# Audio_Devices.net
KiCad netlist of a schematic drawn in Altium Designer
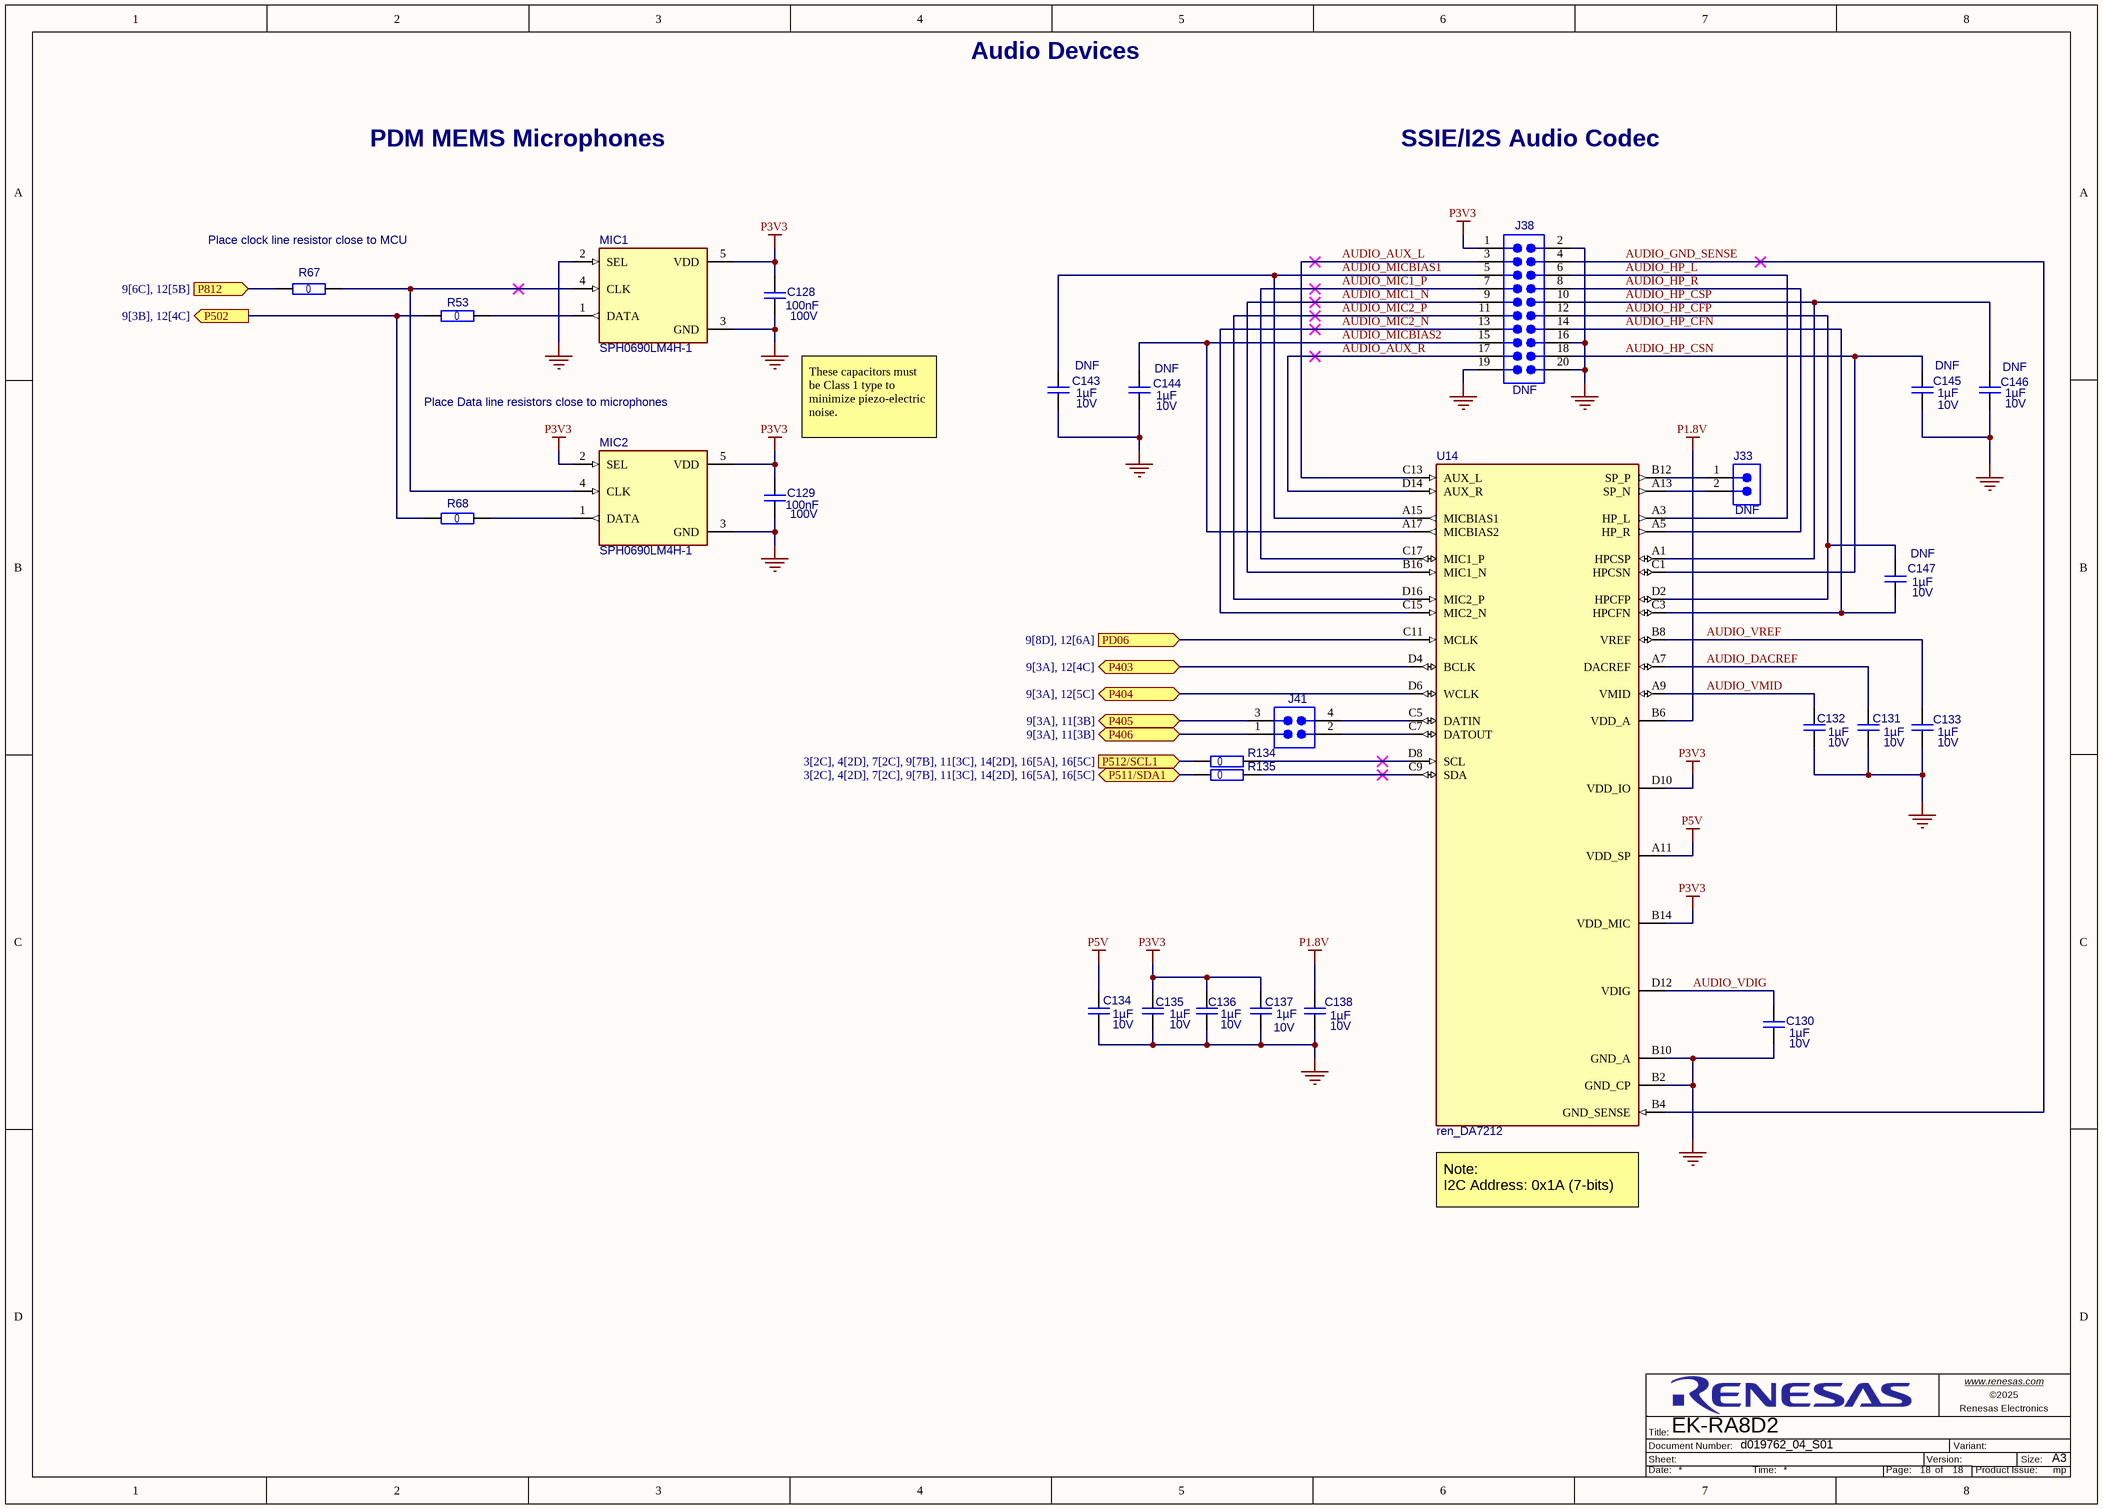
[diagram p0: Audio Devices.SchDoc]

(export (version "E")
  (design (tool "Eeschema 10.0.6"))
  (components
    (comp (ref "C128")
      (value "100nF")
      (footprint "C_EIA1206_1p8")
      (description "Capacitor,EIA1206,100n,100V,C0G")
      (fields
        (field (name "TOLERANCE") "5%")
        (field (name "OPERATING VOLTAGE MAX") "100V")
        (field (name "Comment") "Capacitor")
      )
      (libsource (lib "ek-ra8d2_mp - Customer") (part "Capacitor"))
    )
    (comp (ref "C129")
      (value "100nF")
      (footprint "C_EIA1206_1p8")
      (description "Capacitor,EIA1206,100n,100V,C0G")
      (fields
        (field (name "TOLERANCE") "5%")
        (field (name "OPERATING VOLTAGE MAX") "100V")
        (field (name "Comment") "Capacitor")
      )
      (libsource (lib "ek-ra8d2_mp - Customer") (part "Capacitor"))
    )
    (comp (ref "C130")
      (value "1µF")
      (footprint "C_EIA0201_0p4")
      (description "Capacitor,EA0201,1u,10V,X6S")
      (fields
        (field (name "TOLERANCE") "20%")
        (field (name "OPERATING VOLTAGE MAX") "10V")
        (field (name "Comment") "Capacitor")
      )
      (libsource (lib "ek-ra8d2_mp - Customer") (part "Capacitor"))
    )
    (comp (ref "C131")
      (value "1µF")
      (footprint "C_EIA0201_0p4")
      (description "Capacitor,EA0201,1u,10V,X6S")
      (fields
        (field (name "TOLERANCE") "20%")
        (field (name "OPERATING VOLTAGE MAX") "10V")
        (field (name "Comment") "Capacitor")
      )
      (libsource (lib "ek-ra8d2_mp - Customer") (part "Capacitor"))
    )
    (comp (ref "C132")
      (value "1µF")
      (footprint "C_EIA0201_0p4")
      (description "Capacitor,EA0201,1u,10V,X6S")
      (fields
        (field (name "TOLERANCE") "20%")
        (field (name "OPERATING VOLTAGE MAX") "10V")
        (field (name "Comment") "Capacitor")
      )
      (libsource (lib "ek-ra8d2_mp - Customer") (part "Capacitor"))
    )
    (comp (ref "C133")
      (value "1µF")
      (footprint "C_EIA0201_0p4")
      (description "Capacitor,EA0201,1u,10V,X6S")
      (fields
        (field (name "TOLERANCE") "20%")
        (field (name "OPERATING VOLTAGE MAX") "10V")
        (field (name "Comment") "Capacitor")
      )
      (libsource (lib "ek-ra8d2_mp - Customer") (part "Capacitor"))
    )
    (comp (ref "C134")
      (value "1µF")
      (footprint "C_EIA0201_0p4")
      (description "Capacitor,EA0201,1u,10V,X6S")
      (fields
        (field (name "TOLERANCE") "20%")
        (field (name "OPERATING VOLTAGE MAX") "10V")
        (field (name "Comment") "Capacitor")
      )
      (libsource (lib "ek-ra8d2_mp - Customer") (part "Capacitor"))
    )
    (comp (ref "C135")
      (value "1µF")
      (footprint "C_EIA0201_0p4")
      (description "Capacitor,EA0201,1u,10V,X6S")
      (fields
        (field (name "TOLERANCE") "20%")
        (field (name "OPERATING VOLTAGE MAX") "10V")
        (field (name "Comment") "Capacitor")
      )
      (libsource (lib "ek-ra8d2_mp - Customer") (part "Capacitor"))
    )
    (comp (ref "C136")
      (value "1µF")
      (footprint "C_EIA0201_0p4")
      (description "Capacitor,EA0201,1u,10V,X6S")
      (fields
        (field (name "TOLERANCE") "20%")
        (field (name "OPERATING VOLTAGE MAX") "10V")
        (field (name "Comment") "Capacitor")
      )
      (libsource (lib "ek-ra8d2_mp - Customer") (part "Capacitor"))
    )
    (comp (ref "C137")
      (value "1µF")
      (footprint "C_EIA0201_0p4")
      (description "Capacitor,EA0201,1u,10V,X6S")
      (fields
        (field (name "TOLERANCE") "20%")
        (field (name "OPERATING VOLTAGE MAX") "10V")
        (field (name "Comment") "Capacitor")
      )
      (libsource (lib "ek-ra8d2_mp - Customer") (part "Capacitor"))
    )
    (comp (ref "C138")
      (value "1µF")
      (footprint "C_EIA0201_0p4")
      (description "Capacitor,EA0201,1u,10V,X6S")
      (fields
        (field (name "TOLERANCE") "20%")
        (field (name "OPERATING VOLTAGE MAX") "10V")
        (field (name "Comment") "Capacitor")
      )
      (libsource (lib "ek-ra8d2_mp - Customer") (part "Capacitor"))
    )
    (comp (ref "C143")
      (value "1µF")
      (footprint "C_EIA0201_0p4")
      (description "Capacitor,EA0201,1u,10V,X6S")
      (fields
        (field (name "TOLERANCE") "20%")
        (field (name "OPERATING VOLTAGE MAX") "10V")
        (field (name "DNF") "DNF")
        (field (name "Comment") "Capacitor")
      )
      (libsource (lib "ek-ra8d2_mp - Customer") (part "Capacitor"))
    )
    (comp (ref "C144")
      (value "1µF")
      (footprint "C_EIA0201_0p4")
      (description "Capacitor,EA0201,1u,10V,X6S")
      (fields
        (field (name "TOLERANCE") "20%")
        (field (name "OPERATING VOLTAGE MAX") "10V")
        (field (name "DNF") "DNF")
        (field (name "Comment") "Capacitor")
      )
      (libsource (lib "ek-ra8d2_mp - Customer") (part "Capacitor"))
    )
    (comp (ref "C145")
      (value "1µF")
      (footprint "C_EIA0201_0p4")
      (description "Capacitor,EA0201,1u,10V,X6S")
      (fields
        (field (name "TOLERANCE") "20%")
        (field (name "OPERATING VOLTAGE MAX") "10V")
        (field (name "DNF") "DNF")
        (field (name "Comment") "Capacitor")
      )
      (libsource (lib "ek-ra8d2_mp - Customer") (part "Capacitor"))
    )
    (comp (ref "C146")
      (value "1µF")
      (footprint "C_EIA0201_0p4")
      (description "Capacitor,EA0201,1u,10V,X6S")
      (fields
        (field (name "TOLERANCE") "20%")
        (field (name "OPERATING VOLTAGE MAX") "10V")
        (field (name "DNF") "DNF")
        (field (name "Comment") "Capacitor")
      )
      (libsource (lib "ek-ra8d2_mp - Customer") (part "Capacitor"))
    )
    (comp (ref "C147")
      (value "1µF")
      (footprint "C_EIA0201_0p4")
      (description "Capacitor,EA0201,1u,10V,X6S")
      (fields
        (field (name "TOLERANCE") "20%")
        (field (name "OPERATING VOLTAGE MAX") "10V")
        (field (name "DNF") "DNF")
        (field (name "Comment") "Capacitor")
      )
      (libsource (lib "ek-ra8d2_mp - Customer") (part "Capacitor"))
    )
    (comp (ref "J33")
      (value "CON_002")
      (footprint "wue_61300211121")
      (description "Header,2way,1row,vertical,2.54mm,THT")
      (fields (field (name "DNF") "DNF"))
      (libsource (lib "ek-ra8d2_mp - Customer") (part "CON_002"))
    )
    (comp (ref "J38")
      (value "62002021121")
      (footprint "wue_62002021121")
      (description "Header,20way,2row,vertical,2.00mm,THT")
      (fields (field (name "DNF") "DNF"))
      (libsource (lib "ek-ra8d2_mp - Customer") (part "CON_020"))
    )
    (comp (ref "J41")
      (value "57202-G52-02ALF")
      (footprint "amp_57202-G52-02ALF")
      (description "Header,4way,2row,vertical,2mm,SMD")
      (libsource (lib "ek-ra8d2_mp - Customer") (part "CON_004"))
    )
    (comp (ref "MIC1")
      (value "SPH0690LM4H-1")
      (footprint "knw_LGA_3.5x2.65")
      (description "Multimode Digital Bottom Port Silicon Digital Microphone with a single bit PDM output")
      (libsource (lib "ek-ra8d2_mp - Customer") (part "knw_SPH0690LM4H-1"))
    )
    (comp (ref "MIC2")
      (value "SPH0690LM4H-1")
      (footprint "knw_LGA_3.5x2.65")
      (description "Multimode Digital Bottom Port Silicon Digital Microphone with a single bit PDM output")
      (libsource (lib "ek-ra8d2_mp - Customer") (part "knw_SPH0690LM4H-1"))
    )
    (comp (ref "R53")
      (value "0")
      (footprint "R_EIA0402")
      (description "Resistor,EIA0402,0,0.0625W")
      (fields (field (name "POWER") "62.5mW") (field (name "TOLERANCE") "5%"))
      (libsource (lib "ek-ra8d2_mp - Customer") (part "Resistor"))
    )
    (comp (ref "R67")
      (value "0")
      (footprint "R_EIA0402")
      (description "Resistor,EIA0402,0,0.0625W")
      (fields (field (name "POWER") "62.5mW") (field (name "TOLERANCE") "5%"))
      (libsource (lib "ek-ra8d2_mp - Customer") (part "Resistor"))
    )
    (comp (ref "R68")
      (value "0")
      (footprint "R_EIA0402")
      (description "Resistor,EIA0402,0,0.0625W")
      (fields (field (name "POWER") "62.5mW") (field (name "TOLERANCE") "5%"))
      (libsource (lib "ek-ra8d2_mp - Customer") (part "Resistor"))
    )
    (comp (ref "R134")
      (value "0")
      (footprint "R_EIA0402")
      (description "Resistor,EIA0402,0,0.0625W")
      (fields (field (name "POWER") "62.5mW") (field (name "TOLERANCE") "5%"))
      (libsource (lib "") (part "Resistor_1"))
    )
    (comp (ref "R135")
      (value "0")
      (footprint "R_EIA0402")
      (description "Resistor,EIA0402,0,0.0625W")
      (fields (field (name "POWER") "62.5mW") (field (name "TOLERANCE") "5%"))
      (libsource (lib "") (part "Resistor_1"))
    )
    (comp (ref "U14")
      (value "ren_DA7212")
      (footprint "ren_34-ball-WL-CSP")
      (description "Ultra-Low Power Stereo Codec")
      (libsource (lib "ek-ra8d2_mp - Customer") (part "ren_DA7212"))
    )
  )
  (nets
    (net (code "1") (name "/AUDIO_AUX_L") (class "Default")
      (node (ref "J38") (pin "3") (pinfunction "3_3") (pintype "passive"))
      (node (ref "U14") (pin "C13") (pinfunction "AUX_L_C13") (pintype "input"))
    )
    (net (code "2") (name "/AUDIO_AUX_R") (class "Default")
      (node (ref "J38") (pin "17") (pinfunction "17_17") (pintype "passive"))
      (node (ref "U14") (pin "D14") (pinfunction "AUX_R_D14") (pintype "input"))
    )
    (net (code "3") (name "/AUDIO_DACREF") (class "Default")
      (node (ref "C131") (pin "1") (pinfunction "1_1") (pintype "passive"))
      (node (ref "U14") (pin "A7") (pinfunction "DACREF_A7") (pintype "bidirectional"))
    )
    (net (code "4") (name "/AUDIO_GND_SENSE") (class "Default")
      (node (ref "J38") (pin "4") (pinfunction "4_4") (pintype "passive"))
      (node (ref "U14") (pin "B4") (pinfunction "GND_SENSE_B4") (pintype "input"))
    )
    (net (code "5") (name "/AUDIO_HP_CFN") (class "Default")
      (node (ref "C147") (pin "2") (pinfunction "2_2") (pintype "passive"))
      (node (ref "J38") (pin "14") (pinfunction "14_14") (pintype "passive"))
      (node (ref "U14") (pin "C3") (pinfunction "HPCFN_C3") (pintype "bidirectional"))
    )
    (net (code "6") (name "/AUDIO_HP_CFP") (class "Default")
      (node (ref "C147") (pin "1") (pinfunction "1_1") (pintype "passive"))
      (node (ref "J38") (pin "12") (pinfunction "12_12") (pintype "passive"))
      (node (ref "U14") (pin "D2") (pinfunction "HPCFP_D2") (pintype "bidirectional"))
    )
    (net (code "7") (name "/AUDIO_HP_CSN") (class "Default")
      (node (ref "C145") (pin "1") (pinfunction "1_1") (pintype "passive"))
      (node (ref "J38") (pin "18") (pinfunction "18_18") (pintype "passive"))
      (node (ref "U14") (pin "C1") (pinfunction "HPCSN_C1") (pintype "bidirectional"))
    )
    (net (code "8") (name "/AUDIO_HP_CSP") (class "Default")
      (node (ref "C146") (pin "1") (pinfunction "1_1") (pintype "passive"))
      (node (ref "J38") (pin "10") (pinfunction "10_10") (pintype "passive"))
      (node (ref "U14") (pin "A1") (pinfunction "HPCSP_A1") (pintype "bidirectional"))
    )
    (net (code "9") (name "/AUDIO_HP_L") (class "Default")
      (node (ref "J38") (pin "6") (pinfunction "6_6") (pintype "passive"))
      (node (ref "U14") (pin "A3") (pinfunction "HP_L_A3") (pintype "output"))
    )
    (net (code "10") (name "/AUDIO_HP_R") (class "Default")
      (node (ref "J38") (pin "8") (pinfunction "8_8") (pintype "passive"))
      (node (ref "U14") (pin "A5") (pinfunction "HP_R_A5") (pintype "output"))
    )
    (net (code "11") (name "/AUDIO_MIC1_N") (class "Default")
      (node (ref "J38") (pin "9") (pinfunction "9_9") (pintype "passive"))
      (node (ref "U14") (pin "B16") (pinfunction "MIC1_N_B16") (pintype "input"))
    )
    (net (code "12") (name "/AUDIO_MIC1_P") (class "Default")
      (node (ref "J38") (pin "7") (pinfunction "7_7") (pintype "passive"))
      (node (ref "U14") (pin "C17") (pinfunction "MIC1_P_C17") (pintype "bidirectional"))
    )
    (net (code "13") (name "/AUDIO_MIC2_N") (class "Default")
      (node (ref "J38") (pin "13") (pinfunction "13_13") (pintype "passive"))
      (node (ref "U14") (pin "C15") (pinfunction "MIC2_N_C15") (pintype "input"))
    )
    (net (code "14") (name "/AUDIO_MIC2_P") (class "Default")
      (node (ref "J38") (pin "11") (pinfunction "11_11") (pintype "passive"))
      (node (ref "U14") (pin "D16") (pinfunction "MIC2_P_D16") (pintype "input"))
    )
    (net (code "15") (name "/AUDIO_MICBIAS1") (class "Default")
      (node (ref "C143") (pin "1") (pinfunction "1_1") (pintype "passive"))
      (node (ref "J38") (pin "5") (pinfunction "5_5") (pintype "passive"))
      (node (ref "U14") (pin "A15") (pinfunction "MICBIAS1_A15") (pintype "output"))
    )
    (net (code "16") (name "/AUDIO_MICBIAS2") (class "Default")
      (node (ref "C144") (pin "1") (pinfunction "1_1") (pintype "passive"))
      (node (ref "J38") (pin "15") (pinfunction "15_15") (pintype "passive"))
      (node (ref "U14") (pin "A17") (pinfunction "MICBIAS2_A17") (pintype "output"))
    )
    (net (code "17") (name "/AUDIO_VDIG") (class "Default")
      (node (ref "C130") (pin "1") (pinfunction "1_1") (pintype "passive"))
      (node (ref "U14") (pin "D12") (pinfunction "VDIG_D12") (pintype "power_in"))
    )
    (net (code "18") (name "/AUDIO_VMID") (class "Default")
      (node (ref "C132") (pin "1") (pinfunction "1_1") (pintype "passive"))
      (node (ref "U14") (pin "A9") (pinfunction "VMID_A9") (pintype "bidirectional"))
    )
    (net (code "19") (name "/AUDIO_VREF") (class "Default")
      (node (ref "C133") (pin "1") (pinfunction "1_1") (pintype "passive"))
      (node (ref "U14") (pin "B8") (pinfunction "VREF_B8") (pintype "bidirectional"))
    )
    (net (code "20") (name "/P403") (class "Default")
      (node (ref "U14") (pin "D4") (pinfunction "BCLK_D4") (pintype "bidirectional"))
    )
    (net (code "21") (name "/P404") (class "Default")
      (node (ref "U14") (pin "D6") (pinfunction "WCLK_D6") (pintype "bidirectional"))
    )
    (net (code "22") (name "/P405") (class "Default")
      (node (ref "J41") (pin "3") (pinfunction "3_3") (pintype "passive"))
    )
    (net (code "23") (name "/P406") (class "Default")
      (node (ref "J41") (pin "1") (pinfunction "1_1") (pintype "passive"))
    )
    (net (code "24") (name "/P502") (class "Default")
      (node (ref "R53") (pin "1") (pinfunction "1_1") (pintype "passive"))
      (node (ref "R68") (pin "1") (pinfunction "1_1") (pintype "passive"))
    )
    (net (code "25") (name "/P511{slash}SDA1") (class "Default")
      (node (ref "R135") (pin "2") (pinfunction "2_2") (pintype "passive"))
    )
    (net (code "26") (name "/P512{slash}SCL1") (class "Default")
      (node (ref "R134") (pin "2") (pinfunction "2_2") (pintype "passive"))
    )
    (net (code "27") (name "/P812") (class "Default")
      (node (ref "R67") (pin "1") (pinfunction "1_1") (pintype "passive"))
    )
    (net (code "28") (name "/PD06") (class "Default")
      (node (ref "U14") (pin "C11") (pinfunction "MCLK_C11") (pintype "input"))
    )
    (net (code "29") (name "GND") (class "Default")
      (node (ref "C128") (pin "2") (pinfunction "2_2") (pintype "passive"))
      (node (ref "C129") (pin "2") (pinfunction "2_2") (pintype "passive"))
      (node (ref "C130") (pin "2") (pinfunction "2_2") (pintype "passive"))
      (node (ref "C131") (pin "2") (pinfunction "2_2") (pintype "passive"))
      (node (ref "C132") (pin "2") (pinfunction "2_2") (pintype "passive"))
      (node (ref "C133") (pin "2") (pinfunction "2_2") (pintype "passive"))
      (node (ref "C134") (pin "2") (pinfunction "2_2") (pintype "passive"))
      (node (ref "C135") (pin "2") (pinfunction "2_2") (pintype "passive"))
      (node (ref "C136") (pin "2") (pinfunction "2_2") (pintype "passive"))
      (node (ref "C137") (pin "2") (pinfunction "2_2") (pintype "passive"))
      (node (ref "C138") (pin "2") (pinfunction "2_2") (pintype "passive"))
      (node (ref "C143") (pin "2") (pinfunction "2_2") (pintype "passive"))
      (node (ref "C144") (pin "2") (pinfunction "2_2") (pintype "passive"))
      (node (ref "C145") (pin "2") (pinfunction "2_2") (pintype "passive"))
      (node (ref "C146") (pin "2") (pinfunction "2_2") (pintype "passive"))
      (node (ref "J38") (pin "16") (pinfunction "16_16") (pintype "passive"))
      (node (ref "J38") (pin "19") (pinfunction "19_19") (pintype "passive"))
      (node (ref "J38") (pin "2") (pinfunction "2_2") (pintype "passive"))
      (node (ref "J38") (pin "20") (pinfunction "20_20") (pintype "passive"))
      (node (ref "MIC1") (pin "2") (pinfunction "SEL_2") (pintype "input"))
      (node (ref "MIC1") (pin "3") (pinfunction "GND_3") (pintype "power_in"))
      (node (ref "MIC2") (pin "3") (pinfunction "GND_3") (pintype "power_in"))
      (node (ref "U14") (pin "B10") (pinfunction "GND_A_B10") (pintype "power_in"))
      (node (ref "U14") (pin "B2") (pinfunction "GND_CP_B2") (pintype "power_in"))
    )
    (net (code "30") (name "Net-(MIC1-CLK)") (class "Default")
      (node (ref "MIC1") (pin "4") (pinfunction "CLK_4") (pintype "input"))
      (node (ref "MIC2") (pin "4") (pinfunction "CLK_4") (pintype "input"))
      (node (ref "R67") (pin "2") (pinfunction "2_2") (pintype "passive"))
    )
    (net (code "31") (name "Net-(MIC1-DATA)") (class "Default")
      (node (ref "MIC1") (pin "1") (pinfunction "DATA_1") (pintype "output"))
      (node (ref "R53") (pin "2") (pinfunction "2_2") (pintype "passive"))
    )
    (net (code "32") (name "Net-(MIC2-DATA)") (class "Default")
      (node (ref "MIC2") (pin "1") (pinfunction "DATA_1") (pintype "output"))
      (node (ref "R68") (pin "2") (pinfunction "2_2") (pintype "passive"))
    )
    (net (code "33") (name "Net-(U14-DATIN)") (class "Default")
      (node (ref "J41") (pin "4") (pinfunction "4_4") (pintype "passive"))
      (node (ref "U14") (pin "C5") (pinfunction "DATIN_C5") (pintype "bidirectional"))
    )
    (net (code "34") (name "Net-(U14-DATOUT)") (class "Default")
      (node (ref "J41") (pin "2") (pinfunction "2_2") (pintype "passive"))
      (node (ref "U14") (pin "C7") (pinfunction "DATOUT_C7") (pintype "bidirectional"))
    )
    (net (code "35") (name "Net-(U14-SCL)") (class "Default")
      (node (ref "R134") (pin "1") (pinfunction "1_1") (pintype "passive"))
      (node (ref "U14") (pin "D8") (pinfunction "SCL_D8") (pintype "input"))
    )
    (net (code "36") (name "Net-(U14-SDA)") (class "Default")
      (node (ref "R135") (pin "1") (pinfunction "1_1") (pintype "passive"))
      (node (ref "U14") (pin "C9") (pinfunction "SDA_C9") (pintype "bidirectional"))
    )
    (net (code "37") (name "Net-(U14-SP_N)") (class "Default")
      (node (ref "J33") (pin "2") (pinfunction "2_2") (pintype "passive"))
      (node (ref "U14") (pin "A13") (pinfunction "SP_N_A13") (pintype "output"))
    )
    (net (code "38") (name "Net-(U14-SP_P)") (class "Default")
      (node (ref "J33") (pin "1") (pinfunction "1_1") (pintype "passive"))
      (node (ref "U14") (pin "B12") (pinfunction "SP_P_B12") (pintype "output"))
    )
    (net (code "39") (name "P1.8V") (class "Default")
      (node (ref "C138") (pin "1") (pinfunction "1_1") (pintype "passive"))
      (node (ref "U14") (pin "B6") (pinfunction "VDD_A_B6") (pintype "power_in"))
    )
    (net (code "40") (name "P3V3") (class "Default")
      (node (ref "C128") (pin "1") (pinfunction "1_1") (pintype "passive"))
      (node (ref "C129") (pin "1") (pinfunction "1_1") (pintype "passive"))
      (node (ref "C135") (pin "1") (pinfunction "1_1") (pintype "passive"))
      (node (ref "C136") (pin "1") (pinfunction "1_1") (pintype "passive"))
      (node (ref "C137") (pin "1") (pinfunction "1_1") (pintype "passive"))
      (node (ref "J38") (pin "1") (pinfunction "1_1") (pintype "passive"))
      (node (ref "MIC1") (pin "5") (pinfunction "VDD_5") (pintype "power_in"))
      (node (ref "MIC2") (pin "2") (pinfunction "SEL_2") (pintype "input"))
      (node (ref "MIC2") (pin "5") (pinfunction "VDD_5") (pintype "power_in"))
      (node (ref "U14") (pin "B14") (pinfunction "VDD_MIC_B14") (pintype "power_in"))
      (node (ref "U14") (pin "D10") (pinfunction "VDD_IO_D10") (pintype "power_in"))
    )
    (net (code "41") (name "P5V") (class "Default")
      (node (ref "C134") (pin "1") (pinfunction "1_1") (pintype "passive"))
      (node (ref "U14") (pin "A11") (pinfunction "VDD_SP_A11") (pintype "power_in"))
    )
  )
)
